# RFRX.net
KiCad netlist of a schematic drawn in Altium Designer
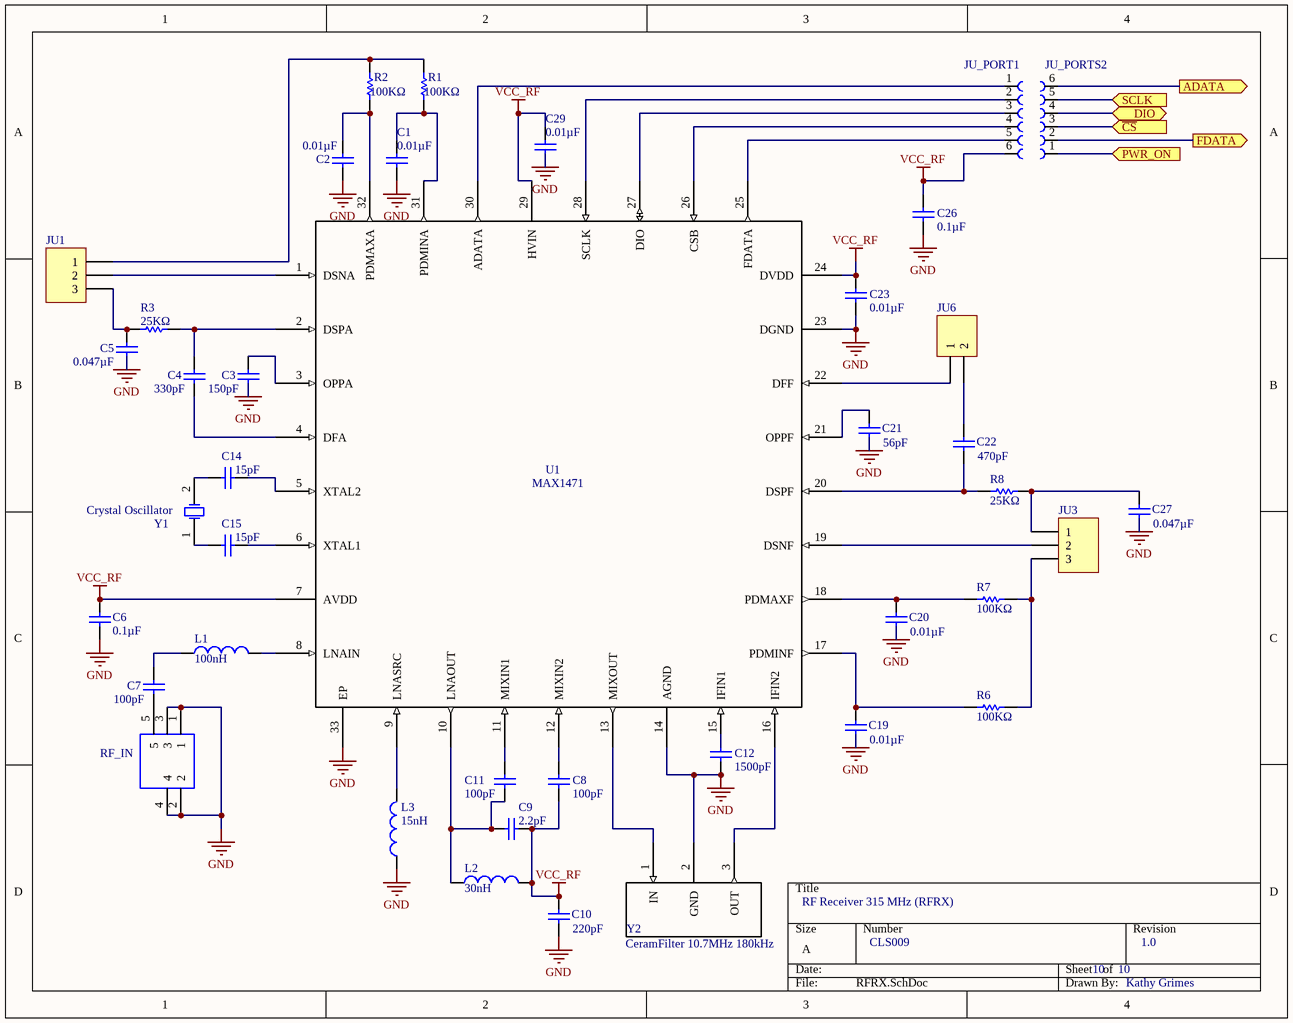
[diagram p0: RFRX.SchDoc]

(export (version "E")
  (design (tool "Eeschema 10.0.6"))
  (components
    (comp (ref "C1")
      (value "0.01µF")
      (footprint "0603_CHIP_FP")
      (description "CAP CER 10000PF 50V X7R 0603")
      (fields
        (field (name "MANUFACTURER") "Murata Electronics North America")
        (field (name "MANUFACTURER PART NUMBER") "GCM188R71H103KA37D")
      )
      (libsource (lib "GenericSymbols") (part "Capacitor_unpolarized_0603"))
    )
    (comp (ref "C2")
      (value "0.01µF")
      (footprint "0603_CHIP_FP")
      (description "CAP CER 10000PF 50V X7R 0603")
      (fields
        (field (name "MANUFACTURER") "Murata Electronics North America")
        (field (name "MANUFACTURER PART NUMBER") "GCM188R71H103KA37D")
      )
      (libsource (lib "GenericSymbols") (part "Capacitor_unpolarized_0603"))
    )
    (comp (ref "C3")
      (value "150pF")
      (footprint "0603_CHIP_FP")
      (description "CAP CER 150PF 100V C0G/NP0 0603")
      (fields
        (field (name "MANUFACTURER") "Murata Electronics North America")
        (field (name "MANUFACTURER PART NUMBER") "GCM1885C2A151JA16D")
      )
      (libsource (lib "GenericSymbols") (part "Capacitor_unpolarized_0603"))
    )
    (comp (ref "C4")
      (value "330pF")
      (footprint "0603_CHIP_FP")
      (description "CAP CER 330PF 100V C0G/NP0 0603")
      (fields
        (field (name "MANUFACTURER") "Murata Electronics North America")
        (field (name "MANUFACTURER PART NUMBER") "GCM1885C2A331JA16D")
      )
      (libsource (lib "GenericSymbols") (part "Capacitor_unpolarized_0603"))
    )
    (comp (ref "C5")
      (value "0.047µF")
      (footprint "0603_CHIP_FP")
      (description "CAP CER 0.047UF 25V X7R 0603")
      (fields
        (field (name "MANUFACTURER") "Murata Electronics North America")
        (field (name "MANUFACTURER PART NUMBER") "GRM188R71E473JA01D")
      )
      (libsource (lib "GenericSymbols") (part "Capacitor_unpolarized_0603"))
    )
    (comp (ref "C6")
      (value "0.1µF")
      (footprint "0603_CHIP_FP")
      (description "CAP CER 0.1UF 100V X7R 0603")
      (fields
        (field (name "MANUFACTURER") "Murata Electronics North America")
        (field (name "MANUFACTURER PART NUMBER") "GRM188R72A104KA35D")
      )
      (libsource (lib "GenericSymbols") (part "Capacitor_unpolarized_0603"))
    )
    (comp (ref "C7")
      (value "100pF")
      (footprint "0603_CHIP_FP")
      (description "CAP CER 100PF 100V C0G/NP0 0603")
      (fields
        (field (name "MANUFACTURER") "Murata Electronics North America")
        (field (name "MANUFACTURER PART NUMBER") "GCM1885C2A101JA16D")
      )
      (libsource (lib "GenericSymbols") (part "Capacitor_unpolarized_0603"))
    )
    (comp (ref "C8")
      (value "100pF")
      (footprint "0603_CHIP_FP")
      (description "CAP CER 100PF 100V C0G/NP0 0603")
      (fields
        (field (name "MANUFACTURER") "Murata Electronics North America")
        (field (name "MANUFACTURER PART NUMBER") "GCM1885C2A101JA16D")
      )
      (libsource (lib "GenericSymbols") (part "Capacitor_unpolarized_0603"))
    )
    (comp (ref "C9")
      (value "2.2pF")
      (footprint "0603_CHIP_FP")
      (description "CAP CER 2.2PF 100V C0G/NP0 0603")
      (fields
        (field (name "MANUFACTURER") "Murata Electronics North America")
        (field (name "MANUFACTURER PART NUMBER") "GQM1885C2A2R2BB01D")
      )
      (libsource (lib "GenericSymbols") (part "Capacitor_unpolarized_0603"))
    )
    (comp (ref "C10")
      (value "220pF")
      (footprint "0603_CHIP_FP")
      (description "CAP CER 220PF 100V X7R 0603")
      (fields
        (field (name "MANUFACTURER") "Murata Electronics North America")
        (field (name "MANUFACTURER PART NUMBER") "GRM188R72A221KA01D")
      )
      (libsource (lib "GenericSymbols") (part "Capacitor_unpolarized_0603"))
    )
    (comp (ref "C11")
      (value "100pF")
      (footprint "0603_CHIP_FP")
      (description "CAP CER 100PF 100V C0G/NP0 0603")
      (fields
        (field (name "MANUFACTURER") "Murata Electronics North America")
        (field (name "MANUFACTURER PART NUMBER") "GCM1885C2A101JA16D")
      )
      (libsource (lib "GenericSymbols") (part "Capacitor_unpolarized_0603"))
    )
    (comp (ref "C12")
      (value "1500pF")
      (footprint "0603_CHIP_FP")
      (description "CAP CER 1500PF 100V X7R 0603")
      (fields
        (field (name "MANUFACTURER") "Murata Electronics North America")
        (field (name "MANUFACTURER PART NUMBER") "GRM188R72A152KA01D")
      )
      (libsource (lib "GenericSymbols") (part "Capacitor_unpolarized_0603"))
    )
    (comp (ref "C14")
      (value "15pF")
      (footprint "0603_CHIP_FP")
      (description "CAP CER 15PF 50V C0G/NP0 0603")
      (fields
        (field (name "MANUFACTURER") "Murata Electronics North America")
        (field (name "MANUFACTURER PART NUMBER") "GQM1885C1H150JB01D")
      )
      (libsource (lib "GenericSymbols") (part "Capacitor_unpolarized_0603"))
    )
    (comp (ref "C15")
      (value "15pF")
      (footprint "0603_CHIP_FP")
      (description "CAP CER 15PF 50V C0G/NP0 0603")
      (fields
        (field (name "MANUFACTURER") "Murata Electronics North America")
        (field (name "MANUFACTURER PART NUMBER") "GQM1885C1H150JB01D")
      )
      (libsource (lib "GenericSymbols") (part "Capacitor_unpolarized_0603"))
    )
    (comp (ref "C19")
      (value "0.01µF")
      (footprint "0603_CHIP_FP")
      (description "CAP CER 10000PF 50V X7R 0603")
      (fields
        (field (name "MANUFACTURER") "Murata Electronics North America")
        (field (name "MANUFACTURER PART NUMBER") "GCM188R71H103KA37D")
      )
      (libsource (lib "GenericSymbols") (part "Capacitor_unpolarized_0603"))
    )
    (comp (ref "C20")
      (value "0.01µF")
      (footprint "0603_CHIP_FP")
      (description "CAP CER 10000PF 50V X7R 0603")
      (fields
        (field (name "MANUFACTURER") "Murata Electronics North America")
        (field (name "MANUFACTURER PART NUMBER") "GCM188R71H103KA37D")
      )
      (libsource (lib "GenericSymbols") (part "Capacitor_unpolarized_0603"))
    )
    (comp (ref "C21")
      (value "56pF")
      (footprint "0603_CHIP_FP")
      (description "CAP CER 56PF 100V C0G/NP0 0603")
      (fields
        (field (name "MANUFACTURER") "Murata Electronics North America")
        (field (name "MANUFACTURER PART NUMBER") "GCM1885C2A560JA16D")
      )
      (libsource (lib "GenericSymbols") (part "Capacitor_unpolarized_0603"))
    )
    (comp (ref "C22")
      (value "470pF")
      (footprint "0603_CHIP_FP")
      (description "CAP CER 470PF 100V C0G/NP0 0603")
      (fields
        (field (name "MANUFACTURER") "Murata Electronics North America")
        (field (name "MANUFACTURER PART NUMBER") "GCM1885C2A471JA16D")
      )
      (libsource (lib "GenericSymbols") (part "Capacitor_unpolarized_0603"))
    )
    (comp (ref "C23")
      (value "0.01µF")
      (footprint "0603_CHIP_FP")
      (description "CAP CER 10000PF 50V X7R 0603")
      (fields
        (field (name "MANUFACTURER") "Murata Electronics North America")
        (field (name "MANUFACTURER PART NUMBER") "GCM188R71H103KA37D")
      )
      (libsource (lib "GenericSymbols") (part "Capacitor_unpolarized_0603"))
    )
    (comp (ref "C26")
      (value "0.1µF")
      (footprint "0603_CHIP_FP")
      (description "CAP CER 0.1UF 100V X7R 0603")
      (fields
        (field (name "MANUFACTURER") "Murata Electronics North America")
        (field (name "MANUFACTURER PART NUMBER") "GRM188R72A104KA35D")
      )
      (libsource (lib "GenericSymbols") (part "Capacitor_unpolarized_0603"))
    )
    (comp (ref "C27")
      (value "0.047µF")
      (footprint "0603_CHIP_FP")
      (description "CAP CER 0.047UF 25V X7R 0603")
      (fields
        (field (name "MANUFACTURER") "Murata Electronics North America")
        (field (name "MANUFACTURER PART NUMBER") "GRM188R71E473JA01D")
      )
      (libsource (lib "GenericSymbols") (part "Capacitor_unpolarized_0603"))
    )
    (comp (ref "C29")
      (value "0.01µF")
      (footprint "0603_CHIP_FP")
      (description "CAP CER 10000PF 50V X7R 0603")
      (fields
        (field (name "MANUFACTURER") "Murata Electronics North America")
        (field (name "MANUFACTURER PART NUMBER") "GCM188R71H103KA37D")
      )
      (libsource (lib "GenericSymbols") (part "Capacitor_unpolarized_0603"))
    )
    (comp (ref "CeramFilter 10.7MHz 180kHz")
      (value "Y2")
      (footprint "SFECV10M7CQ0C01R0")
      (description "Signal Conditioning 10.7MHZ 330 OHM CERA")
      (fields
        (field (name "MANUFACTURER") "Murata Electronics")
        (field (name "MANUFACTURER PART NUMBER") "SFECV10M7FA00-R0")
      )
      (libsource (lib "CeramicFilter") (part "Component_1"))
    )
    (comp (ref "Crystal Oscillator")
      (value "Y1")
      (footprint "XTAL_ECS-100-18-4X")
      (fields
        (field (name "MANUFACTURER") "ECS Inc.")
        (field (name "MANUFACTURER PART NUMBER") "ECS-95.4-S-4")
        (field (name "VENDOR PART NUMBER") "X420-ND")
      )
      (libsource (lib "Miscellaneous Devices") (part "XTAL"))
    )
    (comp (ref "JU1")
      (value "Header 3")
      (footprint "HDR1X3")
      (description "CONN HEADER .100 SINGL STR 36POS")
      (fields (field (name "VENDOR PART NUMBER") "PRT-00116"))
      (libsource (lib "") (part "Header 3_1"))
    )
    (comp (ref "JU3")
      (value "Header 3")
      (footprint "HDR1X3")
      (description "CONN HEADER .100 SINGL STR 36POS")
      (fields (field (name "VENDOR PART NUMBER") "PRT-00116"))
      (libsource (lib "Miscellaneous Connectors") (part "Header 3"))
    )
    (comp (ref "JU6")
      (value "Header 2")
      (footprint "HDR1X2")
      (description "CONN HEADER .100 SINGL STR 36POS")
      (fields (field (name "VENDOR PART NUMBER") "PRT-00116"))
      (libsource (lib "Miscellaneous Connectors") (part "Header 2"))
    )
    (comp (ref "JU_PORT1")
      (value "61300611121")
      (footprint "61300611121")
      (description "Board-To-Board Connector, Vertical, WR-PHD Series, Through Hole, Header, 6, 2.54 mm")
      (fields (field (name "MF") "Wurth Electronics") (field (name "MANUFACTURER") "CONN HEADER 6 POS 2.54"))
      (libsource (lib "61300611121") (part "61300611121"))
    )
    (comp (ref "JU_PORTS2")
      (value "61300611121")
      (footprint "61300611121")
      (description "Board-To-Board Connector, Vertical, WR-PHD Series, Through Hole, Header, 6, 2.54 mm")
      (fields (field (name "MF") "Wurth Electronics") (field (name "MANUFACTURER") "CONN HEADER 6 POS 2.54"))
      (libsource (lib "61300611121") (part "61300611121"))
    )
    (comp (ref "L1")
      (value "100nH")
      (footprint "0603_CHIP_FP")
      (description "FIXED IND 100NH 220MA 680 MOHM")
      (fields
        (field (name "MANUFACTURER") "Murata Electronics North America")
        (field (name "MANUFACTURER PART NUMBER") "LQW18ANR10J00D")
      )
      (libsource (lib "GenericSymbols") (part "Inductor"))
    )
    (comp (ref "L2")
      (value "30nH")
      (footprint "0603_CHIP_FP")
      (description "FIXED IND 30NH 420MA 230 MOHM")
      (fields
        (field (name "MANUFACTURER") "Murata Electronics North America")
        (field (name "MANUFACTURER PART NUMBER") "LQW18AN30NJ00D")
      )
      (libsource (lib "GenericSymbols") (part "Inductor"))
    )
    (comp (ref "L3")
      (value "15nH")
      (footprint "0603_CHIP_FP")
      (description "FIXED IND 15NH 600MA 130 MOHM")
      (fields
        (field (name "MANUFACTURER") "Murata Electronics North America")
        (field (name "MANUFACTURER PART NUMBER") "LQW18AN15NG00D")
      )
      (libsource (lib "GenericSymbols") (part "Inductor"))
    )
    (comp (ref "R1")
      (value "100KΩ")
      (footprint "0603_CHIP_FP")
      (description "RES SMD 100K OHM 1% 1/4W 0603")
      (fields
        (field (name "MANUFACTURER") "Rohm Semiconductor")
        (field (name "MANUFACTURER PART NUMBER") "ESR03EZPF1003")
      )
      (libsource (lib "GenericSymbols") (part "Resistor_0603"))
    )
    (comp (ref "R2")
      (value "100KΩ")
      (footprint "0603_CHIP_FP")
      (description "RES SMD 100K OHM 1% 1/4W 0603")
      (fields
        (field (name "MANUFACTURER") "Rohm Semiconductor")
        (field (name "MANUFACTURER PART NUMBER") "ESR03EZPF1003")
      )
      (libsource (lib "GenericSymbols") (part "Resistor_0603"))
    )
    (comp (ref "R3")
      (value "25KΩ")
      (footprint "0603_CHIP_FP")
      (description "Thin Film Resistors 150mW 25Kohms .1% 25ppm")
      (fields
        (field (name "MANUFACTURER") "Vishay / Thin Film")
        (field (name "MANUFACTURER PART NUMBER") "PNM0603E2502BST1")
      )
      (libsource (lib "GenericSymbols") (part "Resistor_0603"))
    )
    (comp (ref "R6")
      (value "100KΩ")
      (footprint "0603_CHIP_FP")
      (description "RES SMD 100K OHM 1% 1/4W 0603")
      (fields
        (field (name "MANUFACTURER") "Rohm Semiconductor")
        (field (name "MANUFACTURER PART NUMBER") "ESR03EZPF1003")
      )
      (libsource (lib "GenericSymbols") (part "Resistor_0603"))
    )
    (comp (ref "R7")
      (value "100KΩ")
      (footprint "0603_CHIP_FP")
      (description "RES SMD 100K OHM 1% 1/4W 0603")
      (fields
        (field (name "MANUFACTURER") "Rohm Semiconductor")
        (field (name "MANUFACTURER PART NUMBER") "ESR03EZPF1003")
      )
      (libsource (lib "GenericSymbols") (part "Resistor_0603"))
    )
    (comp (ref "R8")
      (value "25KΩ")
      (footprint "0603_CHIP_FP")
      (description "Thin Film Resistors 150mW 25Kohms .1% 25ppm")
      (fields
        (field (name "MANUFACTURER") "Vishay / Thin Film")
        (field (name "MANUFACTURER PART NUMBER") "PNM0603E2502BST1")
      )
      (libsource (lib "GenericSymbols") (part "Resistor_0603"))
    )
    (comp (ref "RF_IN")
      (value "142-0701-201")
      (footprint "142-0701-201")
      (description "CONN SMA JACK STR 50 OHM PCB")
      (fields
        (field (name "MANUFACTURER") "Cinch Connectivity Solutions Johnson")
        (field (name "VENDOR PART NUMBER") "J500-ND")
      )
      (libsource (lib "142-0701-201") (part "142-0701-201"))
    )
    (comp (ref "U1")
      (value "MAX1471")
      (footprint "QFN50P500X500X80-33N")
      (description "RF Receiver 315MHz/434MHz Superheterodyne Rcvr")
      (fields
        (field (name "MANUFACTURER") "Maxim Integrated")
        (field (name "MANUFACTURER PART NUMBER") "MAX1471ATJ+")
      )
      (libsource (lib "QFN50P500X500X80-33N") (part "Component_1"))
    )
  )
  (nets
    (net (code "1") (name "/ADATA") (class "Default")
      (node (ref "JU_PORTS2") (pin "6") (pinfunction "6_6") (pintype "passive"))
    )
    (net (code "2") (name "/DIO") (class "Default")
      (node (ref "JU_PORTS2") (pin "4") (pinfunction "4_4") (pintype "passive"))
    )
    (net (code "3") (name "/FDATA") (class "Default")
      (node (ref "JU_PORTS2") (pin "2") (pinfunction "2_2") (pintype "passive"))
    )
    (net (code "4") (name "/PWR_ON") (class "Default")
      (node (ref "JU_PORTS2") (pin "1") (pinfunction "1_1") (pintype "passive"))
    )
    (net (code "5") (name "/SCLK") (class "Default")
      (node (ref "JU_PORTS2") (pin "5") (pinfunction "5_5") (pintype "passive"))
    )
    (net (code "6") (name "/~{CS}") (class "Default")
      (node (ref "JU_PORTS2") (pin "3") (pinfunction "3_3") (pintype "passive"))
    )
    (net (code "7") (name "GND") (class "Default")
      (node (ref "C1") (pin "1") (pinfunction "1_1") (pintype "passive"))
      (node (ref "C10") (pin "1") (pinfunction "1_1") (pintype "passive"))
      (node (ref "C12") (pin "1") (pinfunction "1_1") (pintype "passive"))
      (node (ref "C19") (pin "1") (pinfunction "1_1") (pintype "passive"))
      (node (ref "C2") (pin "1") (pinfunction "1_1") (pintype "passive"))
      (node (ref "C20") (pin "1") (pinfunction "1_1") (pintype "passive"))
      (node (ref "C21") (pin "1") (pinfunction "1_1") (pintype "passive"))
      (node (ref "C23") (pin "1") (pinfunction "1_1") (pintype "passive"))
      (node (ref "C26") (pin "1") (pinfunction "1_1") (pintype "passive"))
      (node (ref "C27") (pin "1") (pinfunction "1_1") (pintype "passive"))
      (node (ref "C29") (pin "1") (pinfunction "1_1") (pintype "passive"))
      (node (ref "C3") (pin "2") (pinfunction "2_2") (pintype "passive"))
      (node (ref "C5") (pin "1") (pinfunction "1_1") (pintype "passive"))
      (node (ref "C6") (pin "2") (pinfunction "2_2") (pintype "passive"))
      (node (ref "CeramFilter 10.7MHz 180kHz") (pin "2") (pinfunction "GND_2") (pintype "power_in"))
      (node (ref "L3") (pin "1") (pinfunction "1_1") (pintype "passive"))
      (node (ref "RF_IN") (pin "1") (pinfunction "1_1") (pintype "passive"))
      (node (ref "RF_IN") (pin "2") (pinfunction "2_2") (pintype "passive"))
      (node (ref "RF_IN") (pin "3") (pinfunction "3_3") (pintype "passive"))
      (node (ref "RF_IN") (pin "4") (pinfunction "4_4") (pintype "passive"))
      (node (ref "U1") (pin "14") (pinfunction "AGND_14") (pintype "power_in"))
      (node (ref "U1") (pin "23") (pinfunction "DGND_23") (pintype "power_in"))
      (node (ref "U1") (pin "33") (pinfunction "EP_33") (pintype "power_in"))
    )
    (net (code "8") (name "Net-(C5-Pad2)") (class "Default")
      (node (ref "C5") (pin "2") (pinfunction "2_2") (pintype "passive"))
      (node (ref "JU1") (pin "3") (pinfunction "3_3") (pintype "passive"))
      (node (ref "R3") (pin "2") (pinfunction "2_2") (pintype "passive"))
    )
    (net (code "9") (name "Net-(C7-Pad1)") (class "Default")
      (node (ref "C7") (pin "1") (pinfunction "1_1") (pintype "passive"))
      (node (ref "L1") (pin "1") (pinfunction "1_1") (pintype "passive"))
    )
    (net (code "10") (name "Net-(C7-Pad2)") (class "Default")
      (node (ref "C7") (pin "2") (pinfunction "2_2") (pintype "passive"))
      (node (ref "RF_IN") (pin "5") (pinfunction "5_5") (pintype "passive"))
    )
    (net (code "11") (name "Net-(C22-Pad2)") (class "Default")
      (node (ref "C22") (pin "2") (pinfunction "2_2") (pintype "passive"))
      (node (ref "JU6") (pin "2") (pinfunction "2_2") (pintype "passive"))
    )
    (net (code "12") (name "Net-(C27-Pad2)") (class "Default")
      (node (ref "C27") (pin "2") (pinfunction "2_2") (pintype "passive"))
      (node (ref "JU3") (pin "1") (pinfunction "1_1") (pintype "passive"))
      (node (ref "R8") (pin "1") (pinfunction "1_1") (pintype "passive"))
    )
    (net (code "13") (name "Net-(CeramFilter 10.7MHz 180kHz-IN)") (class "Default")
      (node (ref "CeramFilter 10.7MHz 180kHz") (pin "1") (pinfunction "IN_1") (pintype "input"))
      (node (ref "U1") (pin "13") (pinfunction "MIXOUT_13") (pintype "output"))
    )
    (net (code "14") (name "Net-(CeramFilter 10.7MHz 180kHz-OUT)") (class "Default")
      (node (ref "CeramFilter 10.7MHz 180kHz") (pin "3") (pinfunction "OUT_3") (pintype "output"))
      (node (ref "U1") (pin "16") (pinfunction "IFIN2_16") (pintype "input"))
    )
    (net (code "15") (name "Net-(Crystal Oscillator-OSC1)") (class "Default")
      (node (ref "C15") (pin "2") (pinfunction "2_2") (pintype "passive"))
      (node (ref "Crystal Oscillator") (pin "1") (pinfunction "OSC1_1") (pintype "passive"))
    )
    (net (code "16") (name "Net-(Crystal Oscillator-OSC2)") (class "Default")
      (node (ref "C14") (pin "2") (pinfunction "2_2") (pintype "passive"))
      (node (ref "Crystal Oscillator") (pin "2") (pinfunction "OSC2_2") (pintype "passive"))
    )
    (net (code "17") (name "Net-(JU1-Pad1)") (class "Default")
      (node (ref "JU1") (pin "1") (pinfunction "1_1") (pintype "passive"))
      (node (ref "R1") (pin "2") (pinfunction "2_2") (pintype "passive"))
      (node (ref "R2") (pin "2") (pinfunction "2_2") (pintype "passive"))
    )
    (net (code "18") (name "Net-(JU3-Pad3)") (class "Default")
      (node (ref "JU3") (pin "3") (pinfunction "3_3") (pintype "passive"))
      (node (ref "R6") (pin "1") (pinfunction "1_1") (pintype "passive"))
      (node (ref "R7") (pin "1") (pinfunction "1_1") (pintype "passive"))
    )
    (net (code "19") (name "Net-(U1-ADATA)") (class "Default")
      (node (ref "JU_PORT1") (pin "1") (pinfunction "1_1") (pintype "passive"))
      (node (ref "U1") (pin "30") (pinfunction "ADATA_30") (pintype "output"))
    )
    (net (code "20") (name "Net-(U1-CSB)") (class "Default")
      (node (ref "JU_PORT1") (pin "4") (pinfunction "4_4") (pintype "passive"))
      (node (ref "U1") (pin "26") (pinfunction "CSB_26") (pintype "input"))
    )
    (net (code "21") (name "Net-(U1-DFA)") (class "Default")
      (node (ref "C4") (pin "2") (pinfunction "2_2") (pintype "passive"))
      (node (ref "U1") (pin "4") (pinfunction "DFA_4") (pintype "input"))
    )
    (net (code "22") (name "Net-(U1-DFF)") (class "Default")
      (node (ref "JU6") (pin "1") (pinfunction "1_1") (pintype "passive"))
      (node (ref "U1") (pin "22") (pinfunction "DFF_22") (pintype "input"))
    )
    (net (code "23") (name "Net-(U1-DIO)") (class "Default")
      (node (ref "JU_PORT1") (pin "3") (pinfunction "3_3") (pintype "passive"))
      (node (ref "U1") (pin "27") (pinfunction "DIO_27") (pintype "bidirectional"))
    )
    (net (code "24") (name "Net-(U1-DSNA)") (class "Default")
      (node (ref "JU1") (pin "2") (pinfunction "2_2") (pintype "passive"))
      (node (ref "U1") (pin "1") (pinfunction "DSNA_1") (pintype "input"))
    )
    (net (code "25") (name "Net-(U1-DSNF)") (class "Default")
      (node (ref "JU3") (pin "2") (pinfunction "2_2") (pintype "passive"))
      (node (ref "U1") (pin "19") (pinfunction "DSNF_19") (pintype "input"))
    )
    (net (code "26") (name "Net-(U1-DSPA)") (class "Default")
      (node (ref "C4") (pin "1") (pinfunction "1_1") (pintype "passive"))
      (node (ref "R3") (pin "1") (pinfunction "1_1") (pintype "passive"))
      (node (ref "U1") (pin "2") (pinfunction "DSPA_2") (pintype "input"))
    )
    (net (code "27") (name "Net-(U1-DSPF)") (class "Default")
      (node (ref "C22") (pin "1") (pinfunction "1_1") (pintype "passive"))
      (node (ref "R8") (pin "2") (pinfunction "2_2") (pintype "passive"))
      (node (ref "U1") (pin "20") (pinfunction "DSPF_20") (pintype "input"))
    )
    (net (code "28") (name "Net-(U1-FDATA)") (class "Default")
      (node (ref "JU_PORT1") (pin "5") (pinfunction "5_5") (pintype "passive"))
      (node (ref "U1") (pin "25") (pinfunction "FDATA_25") (pintype "output"))
    )
    (net (code "29") (name "Net-(U1-IFIN1)") (class "Default")
      (node (ref "C12") (pin "2") (pinfunction "2_2") (pintype "passive"))
      (node (ref "U1") (pin "15") (pinfunction "IFIN1_15") (pintype "input"))
    )
    (net (code "30") (name "Net-(U1-LNAIN)") (class "Default")
      (node (ref "L1") (pin "2") (pinfunction "2_2") (pintype "passive"))
      (node (ref "U1") (pin "8") (pinfunction "LNAIN_8") (pintype "input"))
    )
    (net (code "31") (name "Net-(U1-LNAOUT)") (class "Default")
      (node (ref "C11") (pin "1") (pinfunction "1_1") (pintype "passive"))
      (node (ref "C9") (pin "2") (pinfunction "2_2") (pintype "passive"))
      (node (ref "L2") (pin "1") (pinfunction "1_1") (pintype "passive"))
      (node (ref "U1") (pin "10") (pinfunction "LNAOUT_10") (pintype "output"))
    )
    (net (code "32") (name "Net-(U1-LNASRC)") (class "Default")
      (node (ref "L3") (pin "2") (pinfunction "2_2") (pintype "passive"))
      (node (ref "U1") (pin "9") (pinfunction "LNASRC_9") (pintype "input"))
    )
    (net (code "33") (name "Net-(U1-MIXIN1)") (class "Default")
      (node (ref "C11") (pin "2") (pinfunction "2_2") (pintype "passive"))
      (node (ref "U1") (pin "11") (pinfunction "MIXIN1_11") (pintype "input"))
    )
    (net (code "34") (name "Net-(U1-MIXIN2)") (class "Default")
      (node (ref "C8") (pin "2") (pinfunction "2_2") (pintype "passive"))
      (node (ref "U1") (pin "12") (pinfunction "MIXIN2_12") (pintype "input"))
    )
    (net (code "35") (name "Net-(U1-OPPA)") (class "Default")
      (node (ref "C3") (pin "1") (pinfunction "1_1") (pintype "passive"))
      (node (ref "U1") (pin "3") (pinfunction "OPPA_3") (pintype "input"))
    )
    (net (code "36") (name "Net-(U1-OPPF)") (class "Default")
      (node (ref "C21") (pin "2") (pinfunction "2_2") (pintype "passive"))
      (node (ref "U1") (pin "21") (pinfunction "OPPF_21") (pintype "input"))
    )
    (net (code "37") (name "Net-(U1-PDMAXA)") (class "Default")
      (node (ref "C2") (pin "2") (pinfunction "2_2") (pintype "passive"))
      (node (ref "R2") (pin "1") (pinfunction "1_1") (pintype "passive"))
      (node (ref "U1") (pin "32") (pinfunction "PDMAXA_32") (pintype "output"))
    )
    (net (code "38") (name "Net-(U1-PDMAXF)") (class "Default")
      (node (ref "C20") (pin "2") (pinfunction "2_2") (pintype "passive"))
      (node (ref "R7") (pin "2") (pinfunction "2_2") (pintype "passive"))
      (node (ref "U1") (pin "18") (pinfunction "PDMAXF_18") (pintype "output"))
    )
    (net (code "39") (name "Net-(U1-PDMINA)") (class "Default")
      (node (ref "C1") (pin "2") (pinfunction "2_2") (pintype "passive"))
      (node (ref "R1") (pin "1") (pinfunction "1_1") (pintype "passive"))
      (node (ref "U1") (pin "31") (pinfunction "PDMINA_31") (pintype "output"))
    )
    (net (code "40") (name "Net-(U1-PDMINF)") (class "Default")
      (node (ref "C19") (pin "2") (pinfunction "2_2") (pintype "passive"))
      (node (ref "R6") (pin "2") (pinfunction "2_2") (pintype "passive"))
      (node (ref "U1") (pin "17") (pinfunction "PDMINF_17") (pintype "output"))
    )
    (net (code "41") (name "Net-(U1-SCLK)") (class "Default")
      (node (ref "JU_PORT1") (pin "2") (pinfunction "2_2") (pintype "passive"))
      (node (ref "U1") (pin "28") (pinfunction "SCLK_28") (pintype "input"))
    )
    (net (code "42") (name "Net-(U1-XTAL1)") (class "Default")
      (node (ref "C15") (pin "1") (pinfunction "1_1") (pintype "passive"))
      (node (ref "U1") (pin "6") (pinfunction "XTAL1_6") (pintype "input"))
    )
    (net (code "43") (name "Net-(U1-XTAL2)") (class "Default")
      (node (ref "C14") (pin "1") (pinfunction "1_1") (pintype "passive"))
      (node (ref "U1") (pin "5") (pinfunction "XTAL2_5") (pintype "input"))
    )
    (net (code "44") (name "VCC_RF") (class "Default")
      (node (ref "C10") (pin "2") (pinfunction "2_2") (pintype "passive"))
      (node (ref "C23") (pin "2") (pinfunction "2_2") (pintype "passive"))
      (node (ref "C26") (pin "2") (pinfunction "2_2") (pintype "passive"))
      (node (ref "C29") (pin "2") (pinfunction "2_2") (pintype "passive"))
      (node (ref "C6") (pin "1") (pinfunction "1_1") (pintype "passive"))
      (node (ref "C8") (pin "1") (pinfunction "1_1") (pintype "passive"))
      (node (ref "C9") (pin "1") (pinfunction "1_1") (pintype "passive"))
      (node (ref "JU_PORT1") (pin "6") (pinfunction "6_6") (pintype "passive"))
      (node (ref "L2") (pin "2") (pinfunction "2_2") (pintype "passive"))
      (node (ref "U1") (pin "24") (pinfunction "DVDD_24") (pintype "power_in"))
      (node (ref "U1") (pin "29") (pinfunction "HVIN_29") (pintype "power_in"))
      (node (ref "U1") (pin "7") (pinfunction "AVDD_7") (pintype "power_in"))
    )
  )
)
